# SCH_uWaterloo-Circuit-Project_2025-10-19.net
KiCad netlist of a schematic drawn in EasyEDA
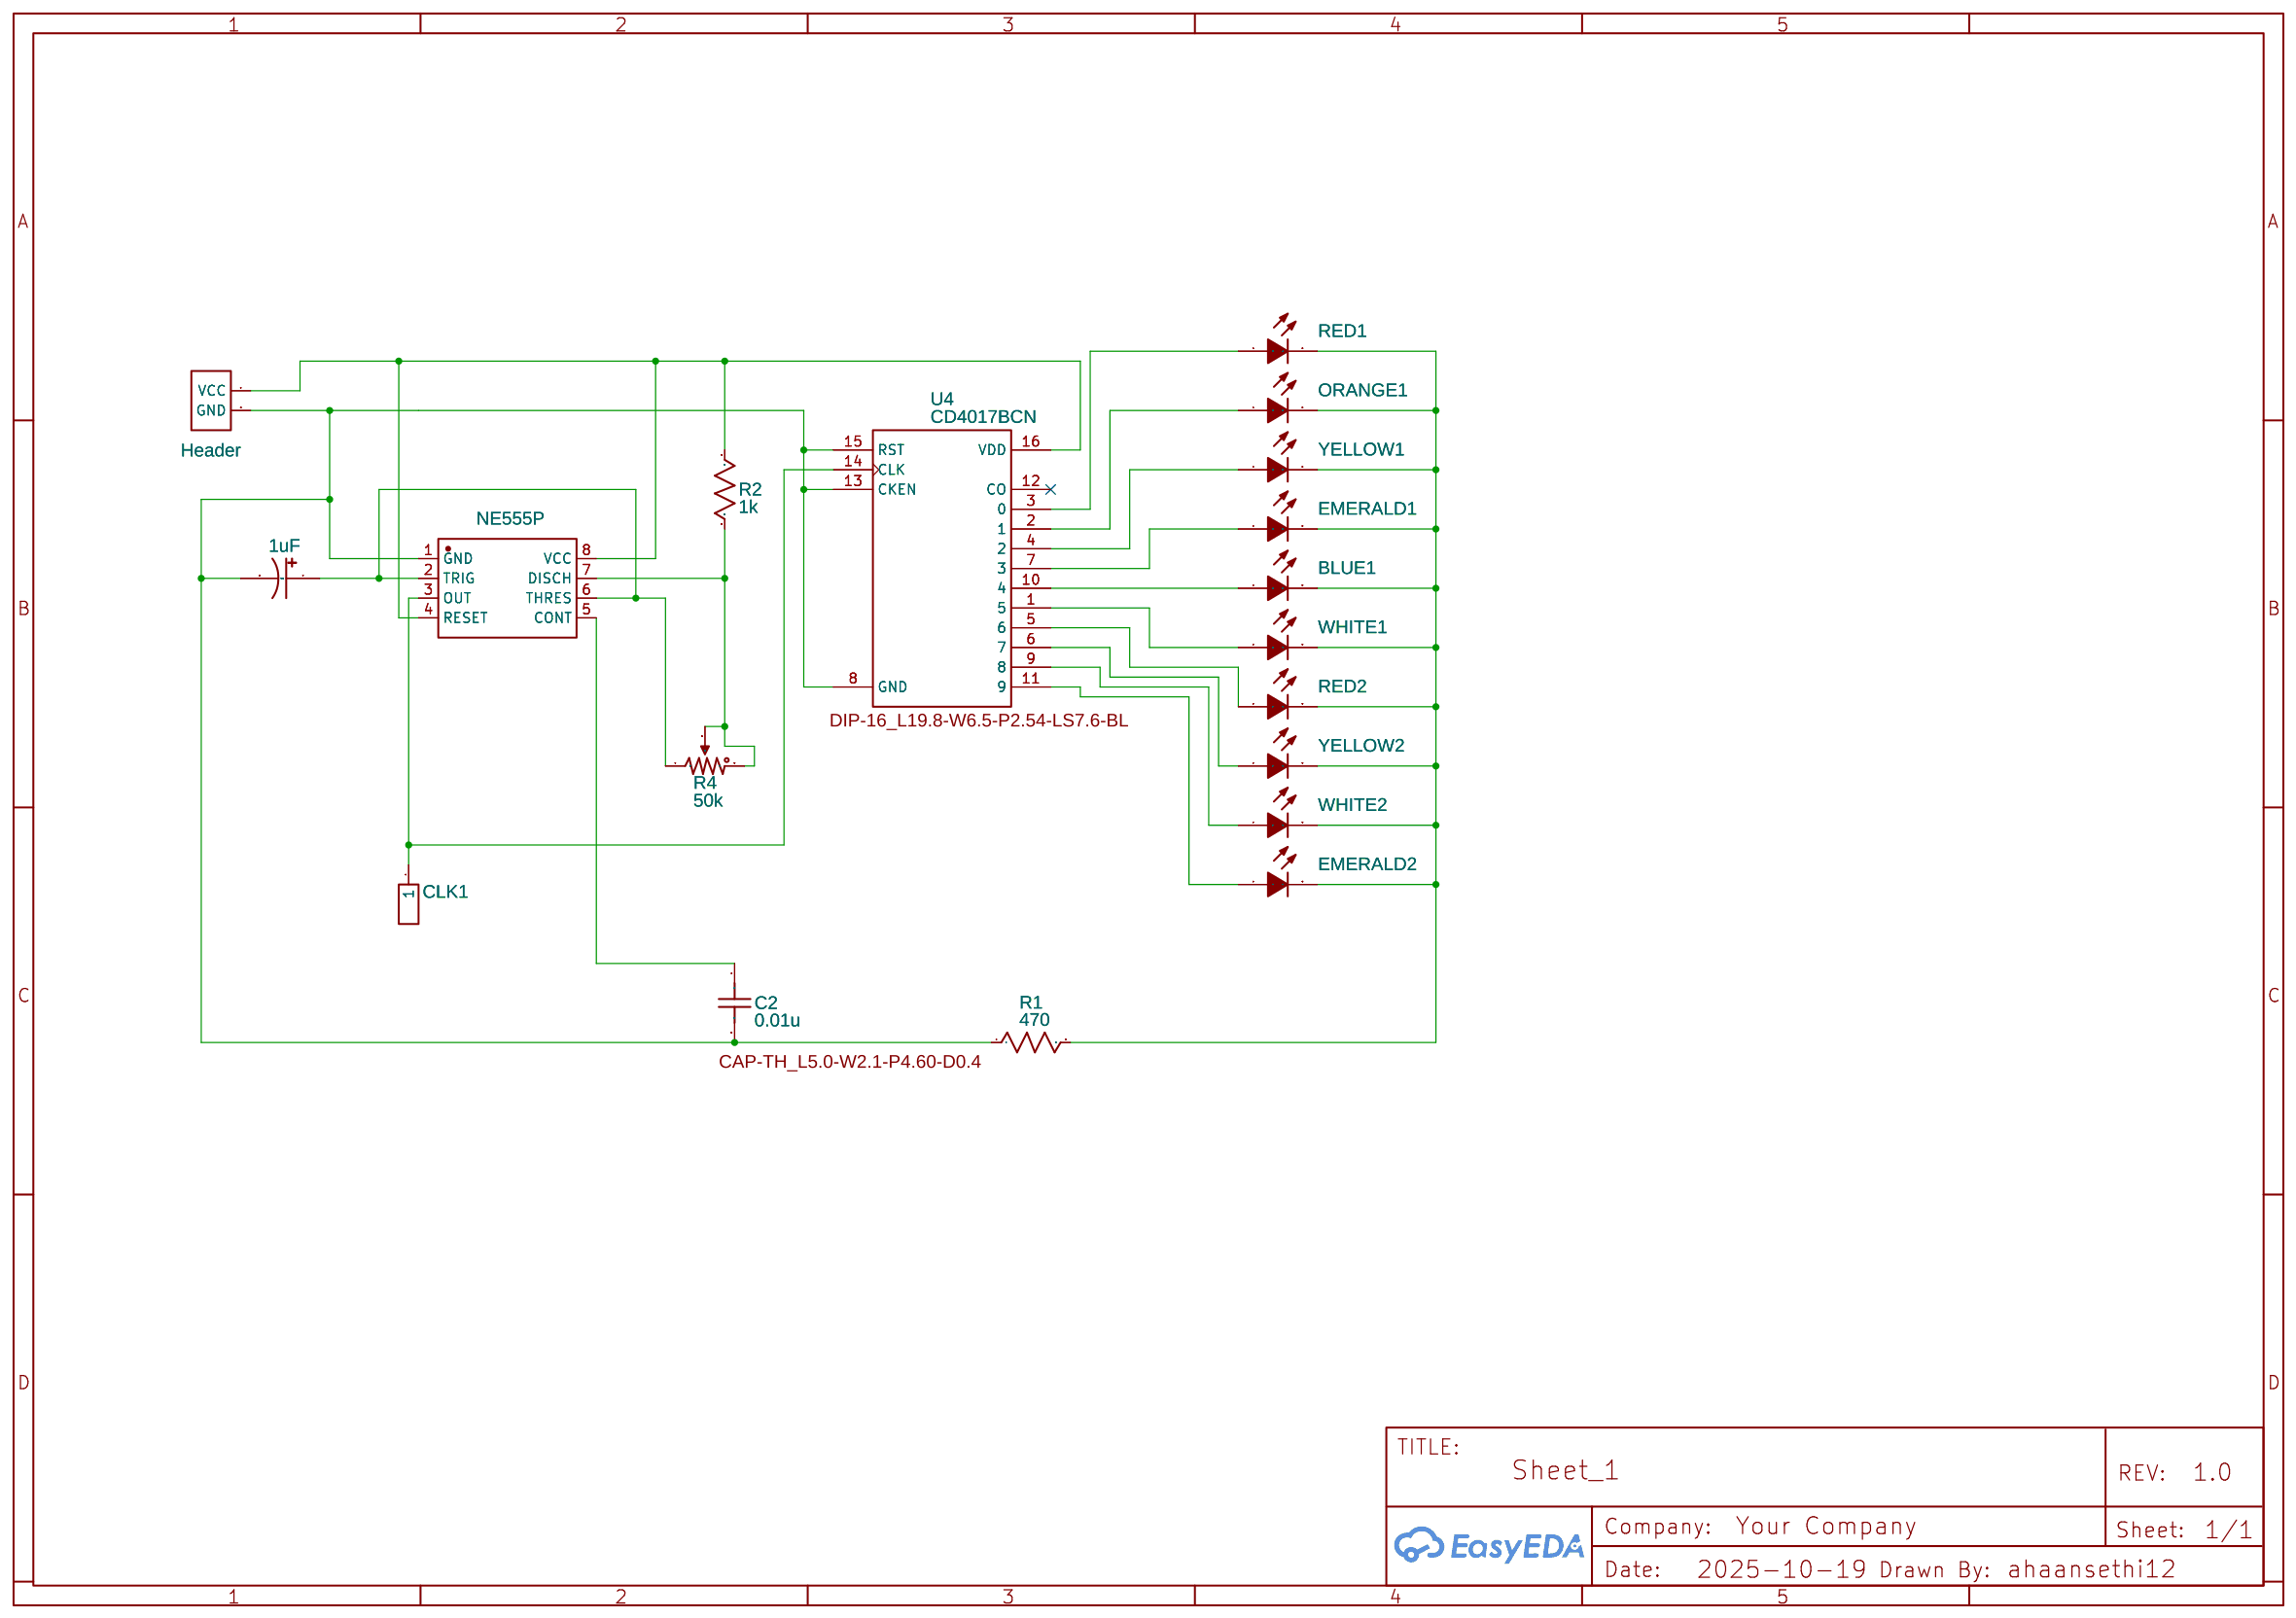
[diagram p0: schematic sheet]

(export (version "E")
  (design (tool "Eeschema 10.0.6"))
  (components
    (comp (ref "BLUE1") (value "LED_5MM") (libsource (lib "") (part "LED_5MM_2")))
    (comp (ref "C1")
      (value "1uF")
      (fields (field (name "Manufacturer Part") "UVZ1H010MDD") (field (name "Manufacturer") "Nichicon(尼吉康)"))
      (libsource (lib "") (part "UVZ1H010MDD"))
    )
    (comp (ref "C2") (value "0.01u") (libsource (lib "") (part "C_0603_US")))
    (comp (ref "CLK1")
      (value "C81276")
      (fields
        (field (name "Manufacturer Part") "2.54-1*1P针")
        (field (name "Manufacturer") "BOOMELE(Boom Precision Elec)")
      )
      (libsource (lib "") (part "Header-Male-2.54_1x1"))
    )
    (comp (ref "EMERALD1") (value "LED_5MM") (libsource (lib "") (part "LED_5MM_4")))
    (comp (ref "EMERALD2") (value "LED_5MM") (libsource (lib "") (part "LED_5MM_4")))
    (comp (ref "H1") (value "Header") (libsource (lib "") (part "HEADER-FEMALE-2.54_1X2")))
    (comp (ref "ORANGE1") (value "LED_5MM") (libsource (lib "") (part "LED_5MM_3")))
    (comp (ref "R1")
      (value "470")
      (fields (field (name "Manufacturer Part") "?"))
      (libsource (lib "") (part "Resistor_1"))
    )
    (comp (ref "R2")
      (value "1k")
      (fields (field (name "Manufacturer Part") "?"))
      (libsource (lib "") (part "Resistor"))
    )
    (comp (ref "R4")
      (value "50k")
      (fields (field (name "Manufacturer Part") "?"))
      (libsource (lib "") (part "Potentiometer"))
    )
    (comp (ref "RED1") (value "LED_5MM") (libsource (lib "") (part "LED_5MM_5")))
    (comp (ref "RED2") (value "LED_5MM") (libsource (lib "") (part "LED_5MM_5")))
    (comp (ref "U2")
      (value "NE555P")
      (fields (field (name "Manufacturer") "TI(德州仪器)"))
      (libsource (lib "") (part "NE555P"))
    )
    (comp (ref "U4") (value "CD4017BCN") (libsource (lib "") (part "CD4017BCN")))
    (comp (ref "WHITE1") (value "LED_5MM") (libsource (lib "") (part "LED_5MM")))
    (comp (ref "WHITE2") (value "LED_5MM") (libsource (lib "") (part "LED_5MM")))
    (comp (ref "YELLOW1") (value "LED_5MM") (libsource (lib "") (part "LED_5MM_1")))
    (comp (ref "YELLOW2") (value "LED_5MM") (libsource (lib "") (part "LED_5MM_1")))
  )
  (nets
    (net (code "1") (name "Net-(BLUE1-A)") (class "Default")
      (node (ref "BLUE1") (pin "1") (pinfunction "A_1") (pintype "input"))
      (node (ref "U4") (pin "10") (pinfunction "4_10") (pintype "output"))
    )
    (net (code "2") (name "Net-(BLUE1-K)") (class "Default")
      (node (ref "BLUE1") (pin "2") (pinfunction "K_2") (pintype "input"))
      (node (ref "EMERALD1") (pin "2") (pinfunction "K_2") (pintype "input"))
      (node (ref "EMERALD2") (pin "2") (pinfunction "K_2") (pintype "input"))
      (node (ref "ORANGE1") (pin "2") (pinfunction "K_2") (pintype "input"))
      (node (ref "R1") (pin "2") (pinfunction "2_2") (pintype "unspecified"))
      (node (ref "RED1") (pin "2") (pinfunction "K_2") (pintype "input"))
      (node (ref "RED2") (pin "2") (pinfunction "K_2") (pintype "input"))
      (node (ref "WHITE1") (pin "2") (pinfunction "K_2") (pintype "input"))
      (node (ref "WHITE2") (pin "2") (pinfunction "K_2") (pintype "input"))
      (node (ref "YELLOW1") (pin "2") (pinfunction "K_2") (pintype "input"))
      (node (ref "YELLOW2") (pin "2") (pinfunction "K_2") (pintype "input"))
    )
    (net (code "3") (name "Net-(EMERALD1-A)") (class "Default")
      (node (ref "EMERALD1") (pin "1") (pinfunction "A_1") (pintype "input"))
      (node (ref "U4") (pin "7") (pinfunction "3_7") (pintype "output"))
    )
    (net (code "4") (name "Net-(EMERALD2-A)") (class "Default")
      (node (ref "EMERALD2") (pin "1") (pinfunction "A_1") (pintype "input"))
      (node (ref "U4") (pin "11") (pinfunction "9_11") (pintype "output"))
    )
    (net (code "5") (name "Net-(H1-GND)") (class "Default")
      (node (ref "C1") (pin "2") (pinfunction "2_2") (pintype "unspecified"))
      (node (ref "C2") (pin "2") (pinfunction "2_2") (pintype "unspecified"))
      (node (ref "H1") (pin "2") (pinfunction "GND_2") (pintype "unspecified"))
      (node (ref "R1") (pin "1") (pinfunction "1_1") (pintype "unspecified"))
      (node (ref "U2") (pin "1") (pinfunction "GND_1") (pintype "unspecified"))
      (node (ref "U4") (pin "13") (pinfunction "CKEN_13") (pintype "unspecified"))
      (node (ref "U4") (pin "15") (pinfunction "RST_15") (pintype "unspecified"))
      (node (ref "U4") (pin "8") (pinfunction "GND_8") (pintype "passive"))
    )
    (net (code "6") (name "Net-(H1-VCC)") (class "Default")
      (node (ref "H1") (pin "1") (pinfunction "VCC_1") (pintype "unspecified"))
      (node (ref "R2") (pin "1") (pinfunction "1_1") (pintype "unspecified"))
      (node (ref "U2") (pin "4") (pinfunction "RESET_4") (pintype "unspecified"))
      (node (ref "U2") (pin "8") (pinfunction "VCC_8") (pintype "unspecified"))
      (node (ref "U4") (pin "16") (pinfunction "VDD_16") (pintype "passive"))
    )
    (net (code "7") (name "Net-(ORANGE1-A)") (class "Default")
      (node (ref "ORANGE1") (pin "1") (pinfunction "A_1") (pintype "input"))
      (node (ref "U4") (pin "2") (pinfunction "1_2") (pintype "output"))
    )
    (net (code "8") (name "Net-(R4-2)") (class "Default")
      (node (ref "R2") (pin "2") (pinfunction "2_2") (pintype "unspecified"))
      (node (ref "R4") (pin "2") (pinfunction "3_2") (pintype "unspecified"))
      (node (ref "R4") (pin "3") (pinfunction "2_3") (pintype "unspecified"))
      (node (ref "U2") (pin "7") (pinfunction "DISCH_7") (pintype "unspecified"))
    )
    (net (code "9") (name "Net-(RED1-A)") (class "Default")
      (node (ref "RED1") (pin "1") (pinfunction "A_1") (pintype "input"))
      (node (ref "U4") (pin "3") (pinfunction "0_3") (pintype "output"))
    )
    (net (code "10") (name "Net-(RED2-A)") (class "Default")
      (node (ref "RED2") (pin "1") (pinfunction "A_1") (pintype "input"))
      (node (ref "U4") (pin "5") (pinfunction "6_5") (pintype "output"))
    )
    (net (code "11") (name "Net-(U2-CONT)") (class "Default")
      (node (ref "C2") (pin "1") (pinfunction "1_1") (pintype "unspecified"))
      (node (ref "U2") (pin "5") (pinfunction "CONT_5") (pintype "unspecified"))
    )
    (net (code "12") (name "Net-(U2-OUT)") (class "Default")
      (node (ref "CLK1") (pin "1") (pinfunction "1_1") (pintype "unspecified"))
      (node (ref "U2") (pin "3") (pinfunction "OUT_3") (pintype "unspecified"))
      (node (ref "U4") (pin "14") (pinfunction "CLK_14") (pintype "unspecified"))
    )
    (net (code "13") (name "Net-(U2-THRES)") (class "Default")
      (node (ref "C1") (pin "1") (pinfunction "1_1") (pintype "unspecified"))
      (node (ref "R4") (pin "1") (pinfunction "1_1") (pintype "unspecified"))
      (node (ref "U2") (pin "2") (pinfunction "TRIG_2") (pintype "unspecified"))
      (node (ref "U2") (pin "6") (pinfunction "THRES_6") (pintype "unspecified"))
    )
    (net (code "14") (name "Net-(U4-2)") (class "Default")
      (node (ref "U4") (pin "4") (pinfunction "2_4") (pintype "output"))
      (node (ref "YELLOW1") (pin "1") (pinfunction "A_1") (pintype "input"))
    )
    (net (code "15") (name "Net-(U4-5)") (class "Default")
      (node (ref "U4") (pin "1") (pinfunction "5_1") (pintype "output"))
      (node (ref "WHITE1") (pin "1") (pinfunction "A_1") (pintype "input"))
    )
    (net (code "16") (name "Net-(U4-7)") (class "Default")
      (node (ref "U4") (pin "6") (pinfunction "7_6") (pintype "output"))
      (node (ref "YELLOW2") (pin "1") (pinfunction "A_1") (pintype "input"))
    )
    (net (code "17") (name "Net-(U4-8)") (class "Default")
      (node (ref "U4") (pin "9") (pinfunction "8_9") (pintype "output"))
      (node (ref "WHITE2") (pin "1") (pinfunction "A_1") (pintype "input"))
    )
    (net (code "18") (name "unconnected-(U4-CO-Pad12)") (class "Default")
      (node (ref "U4") (pin "12") (pinfunction "CO_12") (pintype "output+no_connect"))
    )
  )
)
